# raspberry_interface.net
KiCad netlist of a schematic drawn in Altium Designer
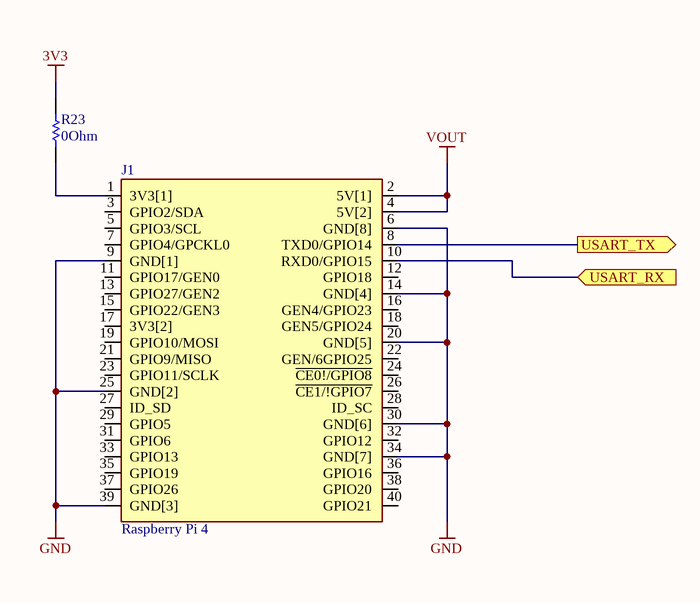
[diagram p0: raspberry_interface.SchDoc]

(export (version "E")
  (design (tool "Eeschema 10.0.6"))
  (components
    (comp (ref "J1")
      (value "Raspberry Pi 4")
      (footprint "40P_HEADER")
      (description "Raspberry Pi 4 with Headers_")
      (fields (field (name "MP") "ADA3708") (field (name "MF") "Raspberry Pi"))
      (libsource (lib "Schlib") (part "RASPBERRY_PI4"))
    )
    (comp (ref "R23")
      (value "0Ohm")
      (footprint "RES_0804")
      (fields (field (name "PART NUMBER") "CRCW120647K0FKEA") (field (name "MANUFACTURER") "Vishay Dale"))
      (libsource (lib "Schlib") (part "RES_0R"))
    )
  )
  (nets
    (net (code "1") (name "/USART_RX") (class "Default")
      (node (ref "J1") (pin "10") (pinfunction "RXD0/GPIO15_10") (pintype "bidirectional"))
    )
    (net (code "2") (name "/USART_TX") (class "Default")
      (node (ref "J1") (pin "8") (pinfunction "TXD0/GPIO14_8") (pintype "bidirectional"))
    )
    (net (code "3") (name "3V3") (class "Default")
      (node (ref "R23") (pin "2") (pinfunction "2_2") (pintype "passive"))
    )
    (net (code "4") (name "GND") (class "Default")
      (node (ref "J1") (pin "14") (pinfunction "GND[4]_14") (pintype "power_in"))
      (node (ref "J1") (pin "20") (pinfunction "GND[5]_20") (pintype "power_in"))
      (node (ref "J1") (pin "25") (pinfunction "GND[2]_25") (pintype "power_in"))
      (node (ref "J1") (pin "30") (pinfunction "GND[6]_30") (pintype "power_in"))
      (node (ref "J1") (pin "34") (pinfunction "GND[7]_34") (pintype "power_in"))
      (node (ref "J1") (pin "39") (pinfunction "GND[3]_39") (pintype "power_in"))
      (node (ref "J1") (pin "6") (pinfunction "GND[8]_6") (pintype "power_in"))
      (node (ref "J1") (pin "9") (pinfunction "GND[1]_9") (pintype "power_in"))
    )
    (net (code "5") (name "Net-(J1-3V3[1])") (class "Default")
      (node (ref "J1") (pin "1") (pinfunction "3V3[1]_1") (pintype "power_in"))
      (node (ref "R23") (pin "1") (pinfunction "1_1") (pintype "passive"))
    )
    (net (code "6") (name "VOUT") (class "Default")
      (node (ref "J1") (pin "2") (pinfunction "5V[1]_2") (pintype "power_in"))
      (node (ref "J1") (pin "4") (pinfunction "5V[2]_4") (pintype "power_in"))
    )
    (net (code "7") (name "unconnected-(J1-3V3[2]-Pad17)") (class "Default")
      (node (ref "J1") (pin "17") (pinfunction "3V3[2]_17") (pintype "power_in"))
    )
    (net (code "8") (name "unconnected-(J1-GEN4{slash}GPIO23-Pad16)") (class "Default")
      (node (ref "J1") (pin "16") (pinfunction "GEN4/GPIO23_16") (pintype "bidirectional"))
    )
    (net (code "9") (name "unconnected-(J1-GEN5{slash}GPIO24-Pad18)") (class "Default")
      (node (ref "J1") (pin "18") (pinfunction "GEN5/GPIO24_18") (pintype "bidirectional"))
    )
    (net (code "10") (name "unconnected-(J1-GEN{slash}6GPIO25-Pad22)") (class "Default")
      (node (ref "J1") (pin "22") (pinfunction "GEN/6GPIO25_22") (pintype "bidirectional"))
    )
    (net (code "11") (name "unconnected-(J1-GPIO2{slash}SDA-Pad3)") (class "Default")
      (node (ref "J1") (pin "3") (pinfunction "GPIO2/SDA_3") (pintype "bidirectional"))
    )
    (net (code "12") (name "unconnected-(J1-GPIO3{slash}SCL-Pad5)") (class "Default")
      (node (ref "J1") (pin "5") (pinfunction "GPIO3/SCL_5") (pintype "bidirectional"))
    )
    (net (code "13") (name "unconnected-(J1-GPIO4{slash}GPCKL0-Pad7)") (class "Default")
      (node (ref "J1") (pin "7") (pinfunction "GPIO4/GPCKL0_7") (pintype "bidirectional"))
    )
    (net (code "14") (name "unconnected-(J1-GPIO5-Pad29)") (class "Default")
      (node (ref "J1") (pin "29") (pinfunction "GPIO5_29") (pintype "bidirectional"))
    )
    (net (code "15") (name "unconnected-(J1-GPIO6-Pad31)") (class "Default")
      (node (ref "J1") (pin "31") (pinfunction "GPIO6_31") (pintype "bidirectional"))
    )
    (net (code "16") (name "unconnected-(J1-GPIO9{slash}MISO-Pad21)") (class "Default")
      (node (ref "J1") (pin "21") (pinfunction "GPIO9/MISO_21") (pintype "bidirectional"))
    )
    (net (code "17") (name "unconnected-(J1-GPIO10{slash}MOSI-Pad19)") (class "Default")
      (node (ref "J1") (pin "19") (pinfunction "GPIO10/MOSI_19") (pintype "bidirectional"))
    )
    (net (code "18") (name "unconnected-(J1-GPIO11{slash}SCLK-Pad23)") (class "Default")
      (node (ref "J1") (pin "23") (pinfunction "GPIO11/SCLK_23") (pintype "bidirectional"))
    )
    (net (code "19") (name "unconnected-(J1-GPIO12-Pad32)") (class "Default")
      (node (ref "J1") (pin "32") (pinfunction "GPIO12_32") (pintype "bidirectional"))
    )
    (net (code "20") (name "unconnected-(J1-GPIO13-Pad33)") (class "Default")
      (node (ref "J1") (pin "33") (pinfunction "GPIO13_33") (pintype "bidirectional"))
    )
    (net (code "21") (name "unconnected-(J1-GPIO16-Pad36)") (class "Default")
      (node (ref "J1") (pin "36") (pinfunction "GPIO16_36") (pintype "bidirectional"))
    )
    (net (code "22") (name "unconnected-(J1-GPIO17{slash}GEN0-Pad11)") (class "Default")
      (node (ref "J1") (pin "11") (pinfunction "GPIO17/GEN0_11") (pintype "bidirectional"))
    )
    (net (code "23") (name "unconnected-(J1-GPIO18-Pad12)") (class "Default")
      (node (ref "J1") (pin "12") (pinfunction "GPIO18_12") (pintype "bidirectional"))
    )
    (net (code "24") (name "unconnected-(J1-GPIO19-Pad35)") (class "Default")
      (node (ref "J1") (pin "35") (pinfunction "GPIO19_35") (pintype "bidirectional"))
    )
    (net (code "25") (name "unconnected-(J1-GPIO20-Pad38)") (class "Default")
      (node (ref "J1") (pin "38") (pinfunction "GPIO20_38") (pintype "bidirectional"))
    )
    (net (code "26") (name "unconnected-(J1-GPIO21-Pad40)") (class "Default")
      (node (ref "J1") (pin "40") (pinfunction "GPIO21_40") (pintype "bidirectional"))
    )
    (net (code "27") (name "unconnected-(J1-GPIO22{slash}GEN3-Pad15)") (class "Default")
      (node (ref "J1") (pin "15") (pinfunction "GPIO22/GEN3_15") (pintype "bidirectional"))
    )
    (net (code "28") (name "unconnected-(J1-GPIO26-Pad37)") (class "Default")
      (node (ref "J1") (pin "37") (pinfunction "GPIO26_37") (pintype "bidirectional"))
    )
    (net (code "29") (name "unconnected-(J1-GPIO27{slash}GEN2-Pad13)") (class "Default")
      (node (ref "J1") (pin "13") (pinfunction "GPIO27/GEN2_13") (pintype "bidirectional"))
    )
    (net (code "30") (name "unconnected-(J1-ID_SC-Pad28)") (class "Default")
      (node (ref "J1") (pin "28") (pinfunction "ID_SC_28") (pintype "bidirectional"))
    )
    (net (code "31") (name "unconnected-(J1-ID_SD-Pad27)") (class "Default")
      (node (ref "J1") (pin "27") (pinfunction "ID_SD_27") (pintype "bidirectional"))
    )
    (net (code "32") (name "unconnected-(J1-~{CE0!{slash}GPIO8}-Pad24)") (class "Default")
      (node (ref "J1") (pin "24") (pinfunction "~{CE0!/GPIO8}_24") (pintype "bidirectional"))
    )
    (net (code "33") (name "unconnected-(J1-~{CE1{slash}!GPIO7}-Pad26)") (class "Default")
      (node (ref "J1") (pin "26") (pinfunction "~{CE1/!GPIO7}_26") (pintype "bidirectional"))
    )
  )
)
